# kotel.net
KiCad netlist of a schematic drawn in EAGLE
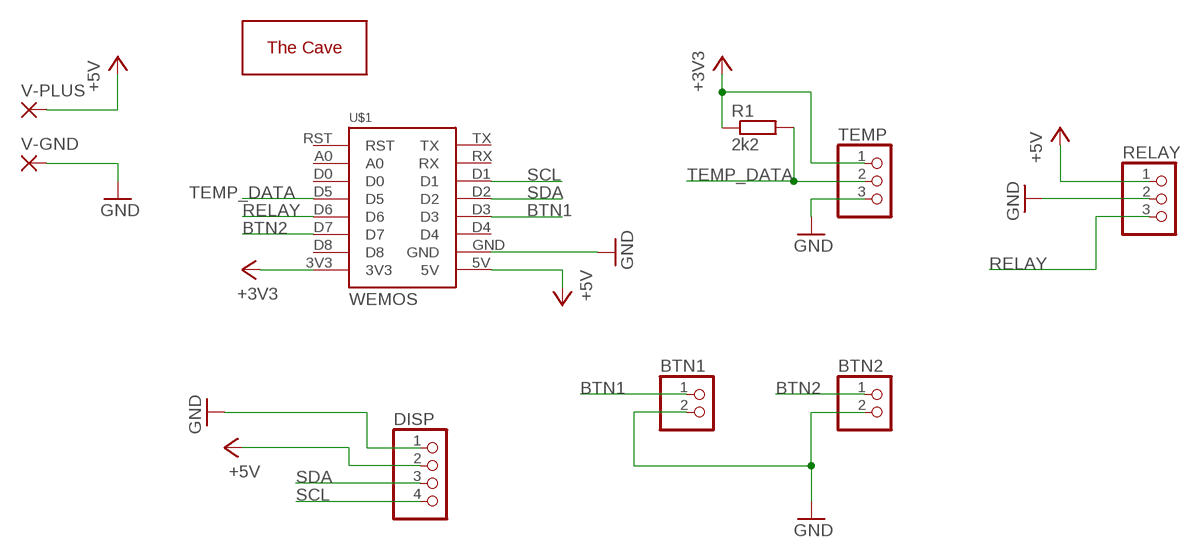
[diagram p0: schematic, sheet 1]

(export (version "E")
  (design (tool "Eeschema 10.0.6"))
  (components
    (comp (ref "BTN1")
      (value "PINHD-1X2")
      (footprint "eagle-import:1X02")
      (libsource (lib "eagle-import") (part "PINHD-1X2"))
    )
    (comp (ref "BTN2")
      (value "PINHD-1X2")
      (footprint "eagle-import:1X02")
      (libsource (lib "eagle-import") (part "PINHD-1X2"))
    )
    (comp (ref "DISP")
      (value "PINHD-1X4")
      (footprint "eagle-import:1X04")
      (libsource (lib "eagle-import") (part "PINHD-1X4"))
    )
    (comp (ref "R1")
      (value "2k2")
      (footprint "eagle-import:0207_7")
      (libsource (lib "eagle-import") (part "R-EU_0207/7"))
    )
    (comp (ref "RELAY")
      (value "PINHD-1X3")
      (footprint "eagle-import:1X03")
      (libsource (lib "eagle-import") (part "PINHD-1X3"))
    )
    (comp (ref "TEMP")
      (value "PINHD-1X3")
      (footprint "eagle-import:1X03")
      (libsource (lib "eagle-import") (part "PINHD-1X3"))
    )
    (comp (ref "U$1")
      (value "WEMOS")
      (footprint "eagle-import:WEMOS")
      (libsource (lib "eagle-import") (part "WEMOS"))
    )
    (comp (ref "U$2")
      (value "THECAVE_LOGO_COPPER_SMALL")
      (footprint "eagle-import:LOGO_COPPER_SMALL")
      (libsource (lib "eagle-import") (part "THECAVE_LOGO_COPPER_SMALL"))
    )
    (comp (ref "V-GND")
      (value "WIREPAD2,54/0,9")
      (footprint "eagle-import:2,54_0,9")
      (libsource (lib "eagle-import") (part "WIREPAD2,54/0,9"))
    )
    (comp (ref "V-PLUS")
      (value "WIREPAD2,54/0,9")
      (footprint "eagle-import:2,54_0,9")
      (libsource (lib "eagle-import") (part "WIREPAD2,54/0,9"))
    )
  )
  (nets
    (net (code "1") (name "+3V3") (class "Default")
      (node (ref "R1") (pin "1") (pinfunction "1_1") (pintype "passive"))
      (node (ref "TEMP") (pin "1") (pinfunction "1_1") (pintype "passive"))
      (node (ref "U$1") (pin "3V3") (pinfunction "3V3_3V3") (pintype "bidirectional"))
    )
    (net (code "2") (name "+5V") (class "Default")
      (node (ref "DISP") (pin "2") (pinfunction "2_2") (pintype "passive"))
      (node (ref "RELAY") (pin "1") (pinfunction "1_1") (pintype "passive"))
      (node (ref "U$1") (pin "5V") (pinfunction "5V_5V") (pintype "bidirectional"))
      (node (ref "V-PLUS") (pin "1") (pinfunction "P_1") (pintype "passive"))
    )
    (net (code "3") (name "/BTN1") (class "Default")
      (node (ref "BTN1") (pin "1") (pinfunction "1_1") (pintype "passive"))
      (node (ref "U$1") (pin "D3") (pinfunction "D3_D3") (pintype "bidirectional"))
    )
    (net (code "4") (name "/BTN2") (class "Default")
      (node (ref "BTN2") (pin "1") (pinfunction "1_1") (pintype "passive"))
      (node (ref "U$1") (pin "D7") (pinfunction "D7_D7") (pintype "bidirectional"))
    )
    (net (code "5") (name "/RELAY") (class "Default")
      (node (ref "RELAY") (pin "3") (pinfunction "3_3") (pintype "passive"))
      (node (ref "U$1") (pin "D6") (pinfunction "D6_D6") (pintype "bidirectional"))
    )
    (net (code "6") (name "/SCL") (class "Default")
      (node (ref "DISP") (pin "4") (pinfunction "4_4") (pintype "passive"))
      (node (ref "U$1") (pin "D1") (pinfunction "D1_D1") (pintype "bidirectional"))
    )
    (net (code "7") (name "/SDA") (class "Default")
      (node (ref "DISP") (pin "3") (pinfunction "3_3") (pintype "passive"))
      (node (ref "U$1") (pin "D2") (pinfunction "D2_D2") (pintype "bidirectional"))
    )
    (net (code "8") (name "/TEMP_DATA") (class "Default")
      (node (ref "R1") (pin "2") (pinfunction "2_2") (pintype "passive"))
      (node (ref "TEMP") (pin "2") (pinfunction "2_2") (pintype "passive"))
      (node (ref "U$1") (pin "D5") (pinfunction "D5_D5") (pintype "bidirectional"))
    )
    (net (code "9") (name "GND") (class "Default")
      (node (ref "BTN1") (pin "2") (pinfunction "2_2") (pintype "passive"))
      (node (ref "BTN2") (pin "2") (pinfunction "2_2") (pintype "passive"))
      (node (ref "DISP") (pin "1") (pinfunction "1_1") (pintype "passive"))
      (node (ref "RELAY") (pin "2") (pinfunction "2_2") (pintype "passive"))
      (node (ref "TEMP") (pin "3") (pinfunction "3_3") (pintype "passive"))
      (node (ref "U$1") (pin "GND") (pinfunction "GND_GND") (pintype "bidirectional"))
      (node (ref "V-GND") (pin "1") (pinfunction "P_1") (pintype "passive"))
    )
    (net (code "10") (name "unconnected-(U$1-PadA0)") (class "Default")
      (node (ref "U$1") (pin "A0") (pinfunction "A0_A0") (pintype "bidirectional"))
    )
    (net (code "11") (name "unconnected-(U$1-PadD0)") (class "Default")
      (node (ref "U$1") (pin "D0") (pinfunction "D0_D0") (pintype "bidirectional"))
    )
    (net (code "12") (name "unconnected-(U$1-PadD4)") (class "Default")
      (node (ref "U$1") (pin "D4") (pinfunction "D4_D4") (pintype "bidirectional"))
    )
    (net (code "13") (name "unconnected-(U$1-PadD8)") (class "Default")
      (node (ref "U$1") (pin "D8") (pinfunction "D8_D8") (pintype "bidirectional"))
    )
    (net (code "14") (name "unconnected-(U$1-PadRST)") (class "Default")
      (node (ref "U$1") (pin "RST") (pinfunction "RST_RST") (pintype "bidirectional"))
    )
    (net (code "15") (name "unconnected-(U$1-PadRX)") (class "Default")
      (node (ref "U$1") (pin "RX") (pinfunction "RX_RX") (pintype "bidirectional"))
    )
    (net (code "16") (name "unconnected-(U$1-PadTX)") (class "Default")
      (node (ref "U$1") (pin "TX") (pinfunction "TX_TX") (pintype "bidirectional"))
    )
  )
)
